# dry-box-controller.net
KiCad netlist of a schematic drawn in EAGLE
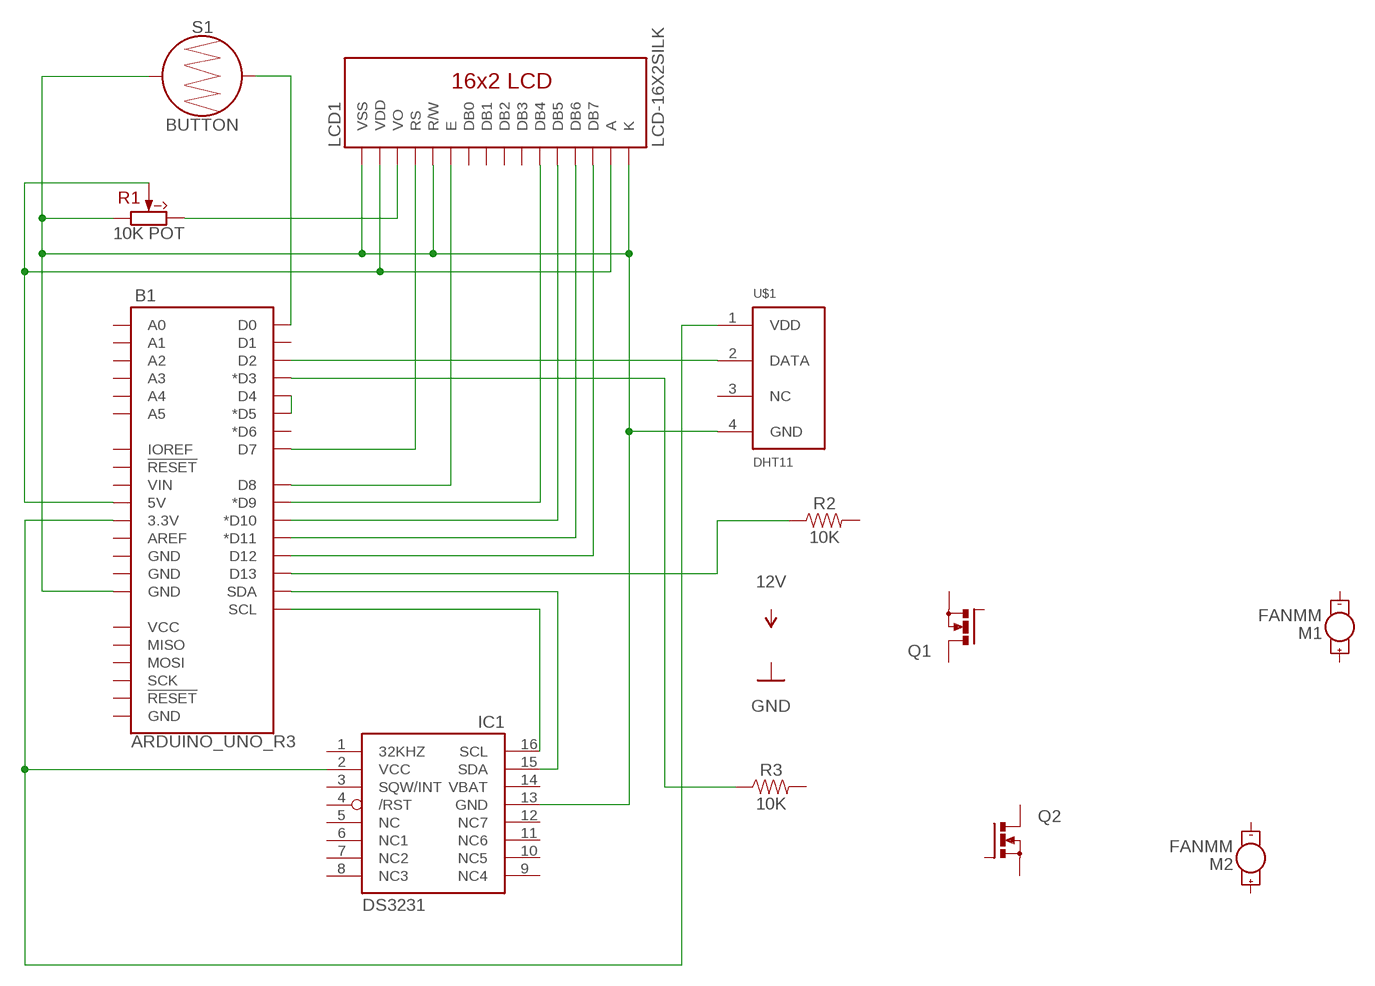
[diagram p0: schematic, sheet 1]

(export (version "E")
  (design (tool "Eeschema 10.0.6"))
  (components
    (comp (ref "B1")
      (value "ARDUINO_UNO_R3")
      (footprint "eagle-import:ARDUINO_R3")
      (libsource (lib "eagle-import") (part "ARDUINO_UNO_R3"))
    )
    (comp (ref "IC1")
      (value "DS3231/SO")
      (footprint "eagle-import:SO16W")
      (fields (field (name "MF") "Maxim Integrated") (field (name "MP") "DS3231"))
      (libsource (lib "eagle-import") (part "DS3231/SO"))
    )
    (comp (ref "LCD1")
      (value "LCD-16X2SILK")
      (footprint "eagle-import:LCD-16X2")
      (libsource (lib "eagle-import") (part "LCD-16X2SILK"))
    )
    (comp (ref "M1")
      (value "FANMM")
      (footprint "eagle-import:VIBE-MOTOR-10MM")
      (libsource (lib "eagle-import") (part "MOTOR10MM"))
    )
    (comp (ref "M2")
      (value "FANMM")
      (footprint "eagle-import:VIBE-MOTOR-10MM")
      (libsource (lib "eagle-import") (part "MOTOR10MM"))
    )
    (comp (ref "Q1")
      (value "PMOSFET_NTO220BV")
      (footprint "eagle-import:TO220BV")
      (libsource (lib "eagle-import") (part "PMOSFET_NTO220BV"))
    )
    (comp (ref "Q2")
      (value "PMOSFET_NTO220BV")
      (footprint "eagle-import:TO220BV")
      (libsource (lib "eagle-import") (part "PMOSFET_NTO220BV"))
    )
    (comp (ref "R1")
      (value "10K POT")
      (footprint "eagle-import:PTD901")
      (libsource (lib "eagle-import") (part "?(PTD90)B20K"))
    )
    (comp (ref "R2")
      (value "10K")
      (footprint "eagle-import:0402")
      (libsource (lib "eagle-import") (part "RESISTOR0402"))
    )
    (comp (ref "R3")
      (value "10K")
      (footprint "eagle-import:0402")
      (libsource (lib "eagle-import") (part "RESISTOR0402"))
    )
    (comp (ref "S1")
      (value "BUTTON")
      (footprint "eagle-import:BUTTON-CONDUCTIVE")
      (libsource (lib "eagle-import") (part "BUTTON-CONDUCTIVESMD"))
    )
    (comp (ref "U$1")
      (value "DHT11")
      (footprint "eagle-import:DHT11")
      (libsource (lib "eagle-import") (part "DHT11"))
    )
  )
  (nets
    (net (code "1") (name "/VBAT") (class "Default")
      (node (ref "IC1") (pin "14") (pinfunction "VBAT_14") (pintype "power_in"))
    )
    (net (code "4") (name "Net-(B1-*D3)") (class "Default")
      (node (ref "B1") (pin "D3") (pinfunction "*D3_D3") (pintype "bidirectional"))
      (node (ref "R3") (pin "1") (pinfunction "1_1") (pintype "passive"))
    )
    (net (code "5") (name "Net-(B1-*D5)") (class "Default")
      (node (ref "B1") (pin "D4") (pinfunction "D4_D4") (pintype "bidirectional"))
      (node (ref "B1") (pin "D5") (pinfunction "*D5_D5") (pintype "bidirectional"))
    )
    (net (code "6") (name "Net-(B1-*D9)") (class "Default")
      (node (ref "B1") (pin "D9") (pinfunction "*D9_D9") (pintype "bidirectional"))
      (node (ref "LCD1") (pin "11") (pinfunction "DB4_11") (pintype "bidirectional"))
    )
    (net (code "7") (name "Net-(B1-*D10)") (class "Default")
      (node (ref "B1") (pin "D10") (pinfunction "*D10_D10") (pintype "bidirectional"))
      (node (ref "LCD1") (pin "12") (pinfunction "DB5_12") (pintype "bidirectional"))
    )
    (net (code "8") (name "Net-(B1-*D11)") (class "Default")
      (node (ref "B1") (pin "D11") (pinfunction "*D11_D11") (pintype "bidirectional"))
      (node (ref "LCD1") (pin "13") (pinfunction "DB6_13") (pintype "bidirectional"))
    )
    (net (code "9") (name "Net-(B1-PadD0)") (class "Default")
      (node (ref "B1") (pin "D0") (pinfunction "D0_D0") (pintype "bidirectional"))
      (node (ref "S1") (pin "2") (pinfunction "2_2") (pintype "passive"))
    )
    (net (code "10") (name "Net-(B1-PadD13)") (class "Default")
      (node (ref "B1") (pin "D13") (pinfunction "D13_D13") (pintype "bidirectional"))
      (node (ref "R2") (pin "1") (pinfunction "1_1") (pintype "passive"))
    )
    (net (code "11") (name "Net-(IC1-GND)") (class "Default")
      (node (ref "B1") (pin "GND@2") (pinfunction "GND_GND@2") (pintype "bidirectional"))
      (node (ref "IC1") (pin "13") (pinfunction "GND_13") (pintype "power_in"))
      (node (ref "LCD1") (pin "1") (pinfunction "VSS_1") (pintype "power_in"))
      (node (ref "LCD1") (pin "16") (pinfunction "K_16") (pintype "power_in"))
      (node (ref "LCD1") (pin "5") (pinfunction "R/W_5") (pintype "input"))
      (node (ref "R1") (pin "1") (pinfunction "CCW_1") (pintype "passive"))
      (node (ref "S1") (pin "1") (pinfunction "1_1") (pintype "passive"))
      (node (ref "U$1") (pin "4") (pinfunction "GND_4") (pintype "power_in"))
    )
    (net (code "12") (name "Net-(IC1-SCL)") (class "Default")
      (node (ref "B1") (pin "SCL") (pinfunction "SCL_SCL") (pintype "bidirectional"))
      (node (ref "IC1") (pin "16") (pinfunction "SCL_16") (pintype "bidirectional"))
    )
    (net (code "13") (name "Net-(IC1-SDA)") (class "Default")
      (node (ref "B1") (pin "SDA") (pinfunction "SDA_SDA") (pintype "bidirectional"))
      (node (ref "IC1") (pin "15") (pinfunction "SDA_15") (pintype "bidirectional"))
    )
    (net (code "14") (name "Net-(IC1-VCC)") (class "Default")
      (node (ref "B1") (pin "3.3V") (pinfunction "3.3V_3.3V") (pintype "bidirectional"))
      (node (ref "IC1") (pin "2") (pinfunction "VCC_2") (pintype "power_in"))
      (node (ref "U$1") (pin "1") (pinfunction "VDD_1") (pintype "power_in"))
    )
    (net (code "15") (name "Net-(LCD1-A)") (class "Default")
      (node (ref "B1") (pin "5V") (pinfunction "5V_5V") (pintype "bidirectional"))
      (node (ref "LCD1") (pin "15") (pinfunction "A_15") (pintype "power_in"))
      (node (ref "LCD1") (pin "2") (pinfunction "VDD_2") (pintype "power_in"))
      (node (ref "R1") (pin "2") (pinfunction "W_2") (pintype "passive"))
    )
    (net (code "16") (name "Net-(LCD1-DB7)") (class "Default")
      (node (ref "B1") (pin "D12") (pinfunction "D12_D12") (pintype "bidirectional"))
      (node (ref "LCD1") (pin "14") (pinfunction "DB7_14") (pintype "bidirectional"))
    )
    (net (code "17") (name "Net-(LCD1-E)") (class "Default")
      (node (ref "B1") (pin "D8") (pinfunction "D8_D8") (pintype "bidirectional"))
      (node (ref "LCD1") (pin "6") (pinfunction "E_6") (pintype "input"))
    )
    (net (code "18") (name "Net-(LCD1-RS)") (class "Default")
      (node (ref "B1") (pin "D7") (pinfunction "D7_D7") (pintype "bidirectional"))
      (node (ref "LCD1") (pin "4") (pinfunction "RS_4") (pintype "input"))
    )
    (net (code "19") (name "Net-(LCD1-VO)") (class "Default")
      (node (ref "LCD1") (pin "3") (pinfunction "VO_3") (pintype "bidirectional"))
      (node (ref "R1") (pin "3") (pinfunction "CW_3") (pintype "passive"))
    )
    (net (code "20") (name "Net-(U$1-DATA)") (class "Default")
      (node (ref "B1") (pin "D2") (pinfunction "D2_D2") (pintype "bidirectional"))
      (node (ref "U$1") (pin "2") (pinfunction "DATA_2") (pintype "bidirectional"))
    )
    (net (code "21") (name "unconnected-(B1-*D6-PadD6)") (class "Default")
      (node (ref "B1") (pin "D6") (pinfunction "*D6_D6") (pintype "bidirectional"))
    )
    (net (code "22") (name "unconnected-(B1-GND-PadGND@1)") (class "Default")
      (node (ref "B1") (pin "GND@1") (pinfunction "GND_GND@1") (pintype "bidirectional"))
    )
    (net (code "23") (name "unconnected-(B1-GND-PadGND@3)") (class "Default")
      (node (ref "B1") (pin "GND@3") (pinfunction "GND_GND@3") (pintype "bidirectional"))
    )
    (net (code "24") (name "unconnected-(B1-GND-PadGND@4)") (class "Default")
      (node (ref "B1") (pin "GND@4") (pinfunction "GND_GND@4") (pintype "bidirectional"))
    )
    (net (code "25") (name "unconnected-(B1-PadA0)") (class "Default")
      (node (ref "B1") (pin "A0") (pinfunction "A0_A0") (pintype "bidirectional"))
    )
    (net (code "26") (name "unconnected-(B1-PadA1)") (class "Default")
      (node (ref "B1") (pin "A1") (pinfunction "A1_A1") (pintype "bidirectional"))
    )
    (net (code "27") (name "unconnected-(B1-PadA2)") (class "Default")
      (node (ref "B1") (pin "A2") (pinfunction "A2_A2") (pintype "bidirectional"))
    )
    (net (code "28") (name "unconnected-(B1-PadA3)") (class "Default")
      (node (ref "B1") (pin "A3") (pinfunction "A3_A3") (pintype "bidirectional"))
    )
    (net (code "29") (name "unconnected-(B1-PadA4)") (class "Default")
      (node (ref "B1") (pin "A4") (pinfunction "A4_A4") (pintype "bidirectional"))
    )
    (net (code "30") (name "unconnected-(B1-PadA5)") (class "Default")
      (node (ref "B1") (pin "A5") (pinfunction "A5_A5") (pintype "bidirectional"))
    )
    (net (code "31") (name "unconnected-(B1-PadAREF)") (class "Default")
      (node (ref "B1") (pin "AREF") (pinfunction "AREF_AREF") (pintype "bidirectional"))
    )
    (net (code "32") (name "unconnected-(B1-PadD1)") (class "Default")
      (node (ref "B1") (pin "D1") (pinfunction "D1_D1") (pintype "bidirectional"))
    )
    (net (code "33") (name "unconnected-(B1-PadIOREF)") (class "Default")
      (node (ref "B1") (pin "IOREF") (pinfunction "IOREF_IOREF") (pintype "bidirectional"))
    )
    (net (code "34") (name "unconnected-(B1-PadMISO)") (class "Default")
      (node (ref "B1") (pin "MISO") (pinfunction "MISO_MISO") (pintype "bidirectional"))
    )
    (net (code "35") (name "unconnected-(B1-PadMOSI)") (class "Default")
      (node (ref "B1") (pin "MOSI") (pinfunction "MOSI_MOSI") (pintype "bidirectional"))
    )
    (net (code "36") (name "unconnected-(B1-PadSCK)") (class "Default")
      (node (ref "B1") (pin "SCK") (pinfunction "SCK_SCK") (pintype "bidirectional"))
    )
    (net (code "37") (name "unconnected-(B1-PadVCC)") (class "Default")
      (node (ref "B1") (pin "VCC") (pinfunction "VCC_VCC") (pintype "bidirectional"))
    )
    (net (code "38") (name "unconnected-(B1-PadVIN)") (class "Default")
      (node (ref "B1") (pin "VIN") (pinfunction "VIN_VIN") (pintype "bidirectional"))
    )
    (net (code "39") (name "unconnected-(B1-~{RESET}-PadRESET@1)") (class "Default")
      (node (ref "B1") (pin "RESET@1") (pinfunction "~{RESET}_RESET@1") (pintype "bidirectional"))
    )
    (net (code "40") (name "unconnected-(B1-~{RESET}-PadRESET@2)") (class "Default")
      (node (ref "B1") (pin "RESET@2") (pinfunction "~{RESET}_RESET@2") (pintype "bidirectional"))
    )
    (net (code "41") (name "unconnected-(IC1-32KHZ-Pad1)") (class "Default")
      (node (ref "IC1") (pin "1") (pinfunction "32KHZ_1") (pintype "output"))
    )
    (net (code "42") (name "unconnected-(IC1-NC-Pad5)") (class "Default")
      (node (ref "IC1") (pin "5") (pinfunction "NC_5") (pintype "no_connect"))
    )
    (net (code "43") (name "unconnected-(IC1-NC1-Pad6)") (class "Default")
      (node (ref "IC1") (pin "6") (pinfunction "NC1_6") (pintype "no_connect"))
    )
    (net (code "44") (name "unconnected-(IC1-NC2-Pad7)") (class "Default")
      (node (ref "IC1") (pin "7") (pinfunction "NC2_7") (pintype "no_connect"))
    )
    (net (code "45") (name "unconnected-(IC1-NC3-Pad8)") (class "Default")
      (node (ref "IC1") (pin "8") (pinfunction "NC3_8") (pintype "no_connect"))
    )
    (net (code "46") (name "unconnected-(IC1-NC4-Pad9)") (class "Default")
      (node (ref "IC1") (pin "9") (pinfunction "NC4_9") (pintype "no_connect"))
    )
    (net (code "47") (name "unconnected-(IC1-NC5-Pad10)") (class "Default")
      (node (ref "IC1") (pin "10") (pinfunction "NC5_10") (pintype "no_connect"))
    )
    (net (code "48") (name "unconnected-(IC1-NC6-Pad11)") (class "Default")
      (node (ref "IC1") (pin "11") (pinfunction "NC6_11") (pintype "no_connect"))
    )
    (net (code "49") (name "unconnected-(IC1-NC7-Pad12)") (class "Default")
      (node (ref "IC1") (pin "12") (pinfunction "NC7_12") (pintype "no_connect"))
    )
    (net (code "50") (name "unconnected-(IC1-SQW{slash}INT-Pad3)") (class "Default")
      (node (ref "IC1") (pin "3") (pinfunction "SQW/INT_3") (pintype "output"))
    )
    (net (code "51") (name "unconnected-(IC1-{slash}RST-Pad4)") (class "Default")
      (node (ref "IC1") (pin "4") (pinfunction "/RST_4") (pintype "passive"))
    )
    (net (code "52") (name "unconnected-(LCD1-DB0-Pad7)") (class "Default")
      (node (ref "LCD1") (pin "7") (pinfunction "DB0_7") (pintype "bidirectional"))
    )
    (net (code "53") (name "unconnected-(LCD1-DB1-Pad8)") (class "Default")
      (node (ref "LCD1") (pin "8") (pinfunction "DB1_8") (pintype "bidirectional"))
    )
    (net (code "54") (name "unconnected-(LCD1-DB2-Pad9)") (class "Default")
      (node (ref "LCD1") (pin "9") (pinfunction "DB2_9") (pintype "bidirectional"))
    )
    (net (code "55") (name "unconnected-(LCD1-DB3-Pad10)") (class "Default")
      (node (ref "LCD1") (pin "10") (pinfunction "DB3_10") (pintype "bidirectional"))
    )
    (net (code "56") (name "unconnected-(M1-Pad+)") (class "Default")
      (node (ref "M1") (pin "+") (pinfunction "+_+") (pintype "bidirectional"))
    )
    (net (code "57") (name "unconnected-(M1-Pad-)") (class "Default")
      (node (ref "M1") (pin "-") (pinfunction "-_-") (pintype "bidirectional"))
    )
    (net (code "58") (name "unconnected-(M2-Pad+)") (class "Default")
      (node (ref "M2") (pin "+") (pinfunction "+_+") (pintype "bidirectional"))
    )
    (net (code "59") (name "unconnected-(M2-Pad-)") (class "Default")
      (node (ref "M2") (pin "-") (pinfunction "-_-") (pintype "bidirectional"))
    )
    (net (code "60") (name "unconnected-(Q1-PadD)") (class "Default")
      (node (ref "Q1") (pin "D") (pinfunction "D_D") (pintype "passive"))
    )
    (net (code "61") (name "unconnected-(Q1-PadG)") (class "Default")
      (node (ref "Q1") (pin "G") (pinfunction "G_G") (pintype "passive"))
    )
    (net (code "62") (name "unconnected-(Q1-PadS)") (class "Default")
      (node (ref "Q1") (pin "S") (pinfunction "S_S") (pintype "passive"))
    )
    (net (code "63") (name "unconnected-(Q2-PadD)") (class "Default")
      (node (ref "Q2") (pin "D") (pinfunction "D_D") (pintype "passive"))
    )
    (net (code "64") (name "unconnected-(Q2-PadG)") (class "Default")
      (node (ref "Q2") (pin "G") (pinfunction "G_G") (pintype "passive"))
    )
    (net (code "65") (name "unconnected-(Q2-PadS)") (class "Default")
      (node (ref "Q2") (pin "S") (pinfunction "S_S") (pintype "passive"))
    )
    (net (code "66") (name "unconnected-(R2-Pad2)") (class "Default")
      (node (ref "R2") (pin "2") (pinfunction "2_2") (pintype "passive"))
    )
    (net (code "67") (name "unconnected-(R3-Pad2)") (class "Default")
      (node (ref "R3") (pin "2") (pinfunction "2_2") (pintype "passive"))
    )
    (net (code "68") (name "unconnected-(U$1-NC-Pad3)") (class "Default")
      (node (ref "U$1") (pin "3") (pinfunction "NC_3") (pintype "bidirectional"))
    )
  )
)
